# PIC32MZ.net
KiCad netlist of a schematic drawn in Altium Designer
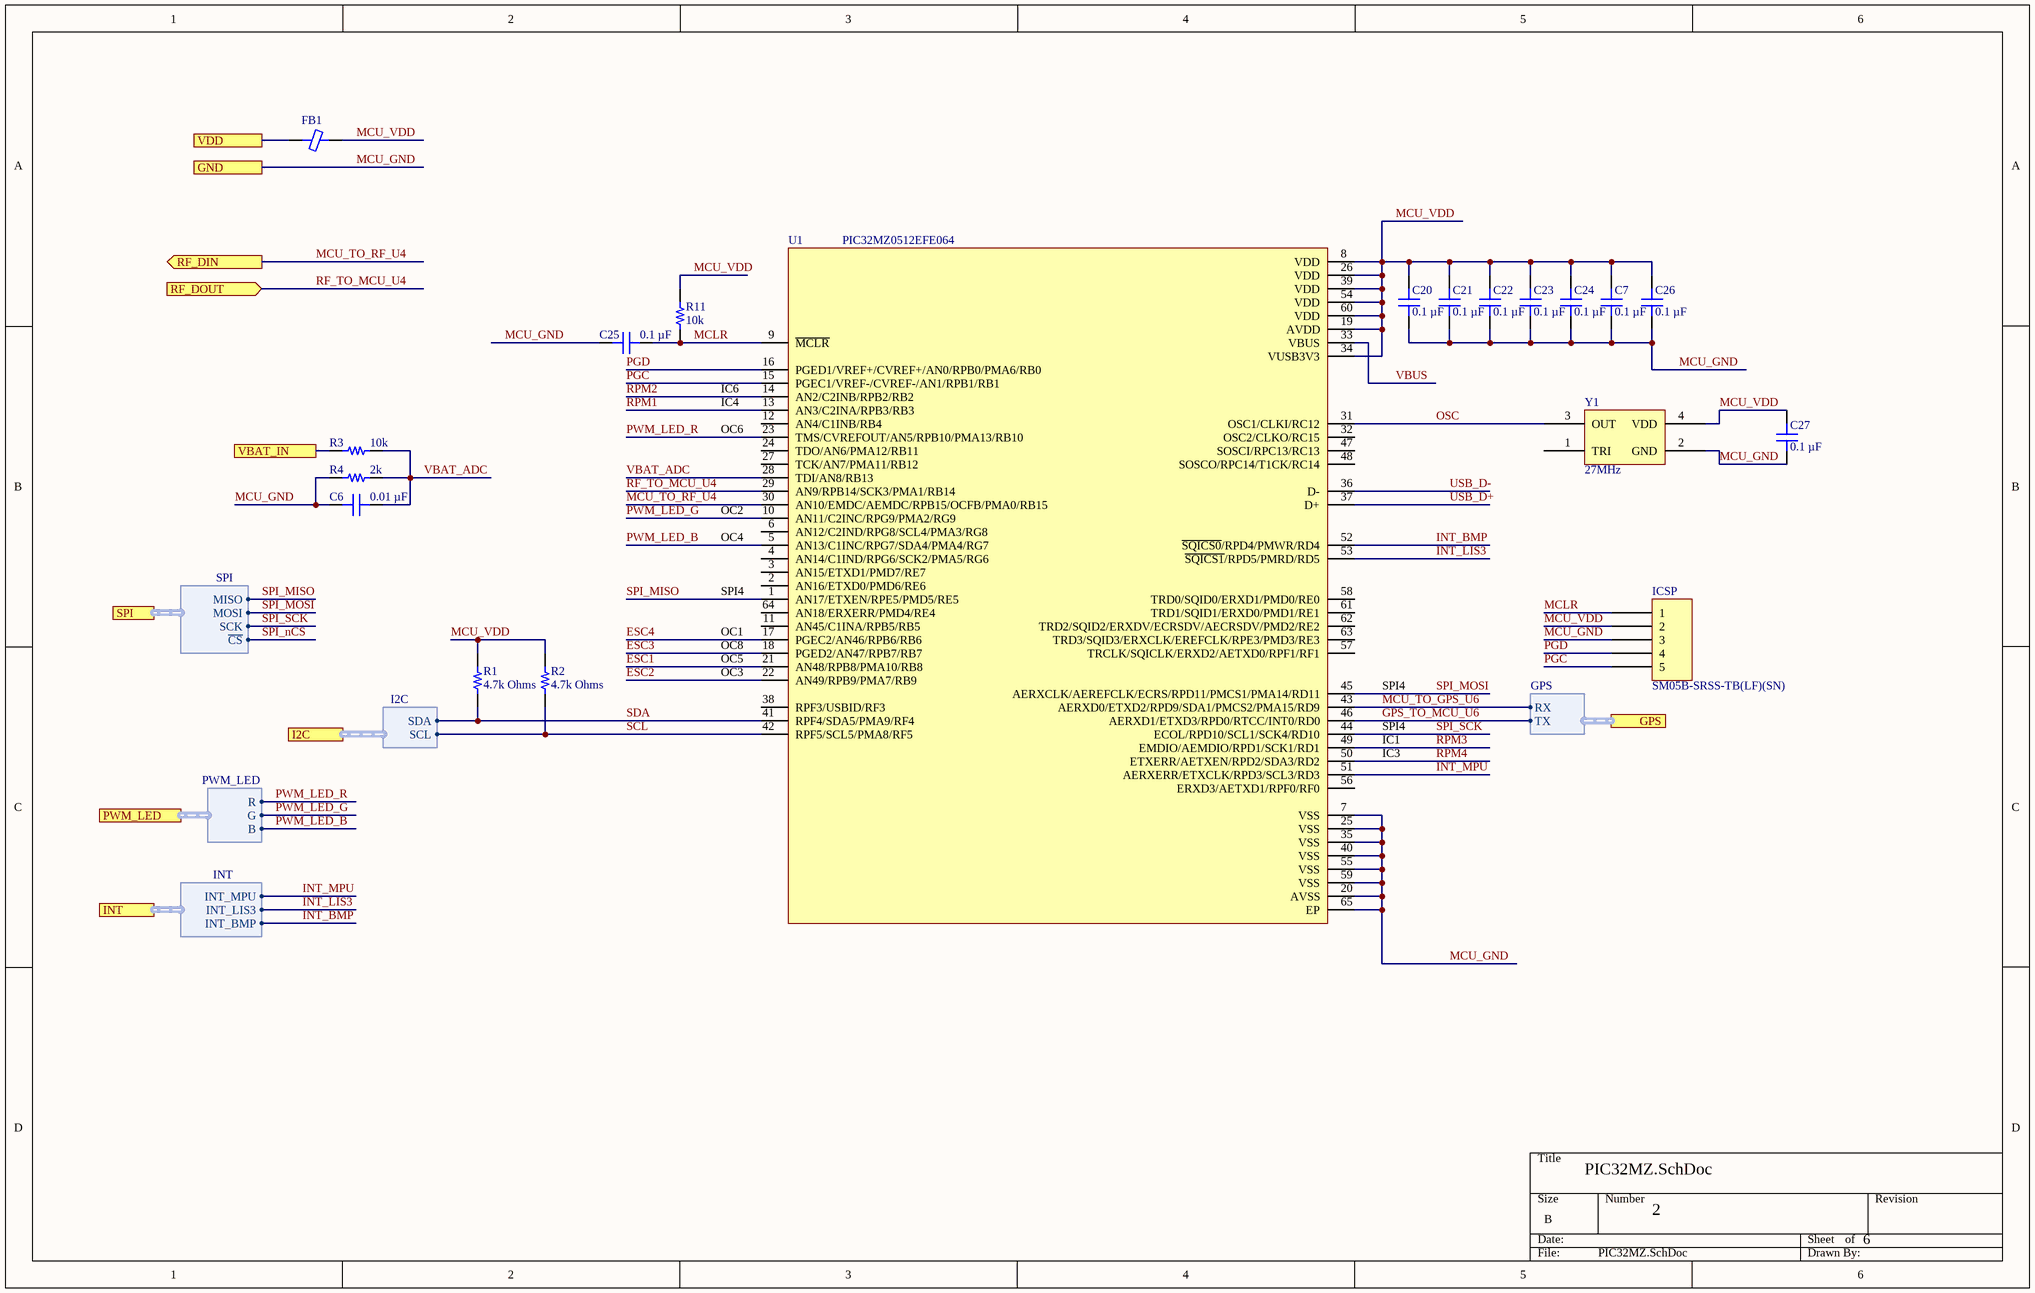
[diagram p0: PIC32MZ.SchDoc]

(export (version "E")
  (design (tool "Eeschema 10.0.6"))
  (components
    (comp (ref "C6")
      (value "0.01 µF")
      (footprint "CAP 0402_1005")
      (description "CAP CER 0.1UF 16V X7R 0402")
      (fields (field (name "PART NUMBER") "C0402C104K4RACAUTO") (field (name "MANUFACTURER") "KEMET"))
      (libsource (lib "Celestial Altium Library - altium_library") (part "Capacitor"))
    )
    (comp (ref "C7")
      (value "0.1 µF")
      (footprint "CAP 0402_1005")
      (description "CAP CER 0.1UF 16V X7R 0402")
      (fields (field (name "PART NUMBER") "C0402C104K4RACAUTO") (field (name "MANUFACTURER") "KEMET"))
      (libsource (lib "Celestial Altium Library - altium_library") (part "Capacitor"))
    )
    (comp (ref "C20")
      (value "0.1 µF")
      (footprint "CAP 0402_1005")
      (description "CAP CER 0.1UF 16V X7R 0402")
      (fields (field (name "PART NUMBER") "C0402C104K4RACAUTO") (field (name "MANUFACTURER") "KEMET"))
      (libsource (lib "Celestial Altium Library - altium_library") (part "Capacitor"))
    )
    (comp (ref "C21")
      (value "0.1 µF")
      (footprint "CAP 0402_1005")
      (description "CAP CER 0.1UF 16V X7R 0402")
      (fields (field (name "PART NUMBER") "C0402C104K4RACAUTO") (field (name "MANUFACTURER") "KEMET"))
      (libsource (lib "Celestial Altium Library - altium_library") (part "Capacitor"))
    )
    (comp (ref "C22")
      (value "0.1 µF")
      (footprint "CAP 0402_1005")
      (description "CAP CER 0.1UF 16V X7R 0402")
      (fields (field (name "PART NUMBER") "C0402C104K4RACAUTO") (field (name "MANUFACTURER") "KEMET"))
      (libsource (lib "Celestial Altium Library - altium_library") (part "Capacitor"))
    )
    (comp (ref "C23")
      (value "0.1 µF")
      (footprint "CAP 0402_1005")
      (description "CAP CER 0.1UF 16V X7R 0402")
      (fields (field (name "PART NUMBER") "C0402C104K4RACAUTO") (field (name "MANUFACTURER") "KEMET"))
      (libsource (lib "Celestial Altium Library - altium_library") (part "Capacitor"))
    )
    (comp (ref "C24")
      (value "0.1 µF")
      (footprint "CAP 0402_1005")
      (description "CAP CER 0.1UF 16V X7R 0402")
      (fields (field (name "PART NUMBER") "C0402C104K4RACAUTO") (field (name "MANUFACTURER") "KEMET"))
      (libsource (lib "Celestial Altium Library - altium_library") (part "Capacitor"))
    )
    (comp (ref "C25")
      (value "0.1 µF")
      (footprint "CAP 0402_1005")
      (description "CAP CER 0.1UF 16V X7R 0402")
      (fields (field (name "PART NUMBER") "C0402C104K4RACAUTO") (field (name "MANUFACTURER") "KEMET"))
      (libsource (lib "Celestial Altium Library - altium_library") (part "Capacitor"))
    )
    (comp (ref "C26")
      (value "0.1 µF")
      (footprint "CAP 0402_1005")
      (description "CAP CER 0.1UF 16V X7R 0402")
      (fields (field (name "PART NUMBER") "C0402C104K4RACAUTO") (field (name "MANUFACTURER") "KEMET"))
      (libsource (lib "Celestial Altium Library - altium_library") (part "Capacitor"))
    )
    (comp (ref "C27")
      (value "0.1 µF")
      (footprint "CAP 0402_1005")
      (description "CAP CER 0.1UF 16V X7R 0402")
      (fields (field (name "PART NUMBER") "C0402C104K4RACAUTO") (field (name "MANUFACTURER") "KEMET"))
      (libsource (lib "Celestial Altium Library - altium_library") (part "Capacitor"))
    )
    (comp (ref "FB1")
      (value "~")
      (footprint "FER 0805_2012")
      (description "FERRITE BEAD 0805 1LN")
      (fields
        (field (name "PART NUMBER") "2508051017Y0")
        (field (name "MANUFACTURER") "Fair-Rite Products Corp.")
      )
      (libsource (lib "Celestial Altium Library - altium_library") (part "Ferrite Chip"))
    )
    (comp (ref "ICSP")
      (value "SM05B-SRSS-TB(LF)(SN)")
      (footprint "JST SM05B-SRSS-TB")
      (description "CONN HEADER SMD R/A 5POS 1MM")
      (fields (field (name "MANUFACTURER") "JST Sales America Inc."))
      (libsource (lib "Celestial Altium Library - altium_library") (part "5 Pin"))
    )
    (comp (ref "R1")
      (value "4.7k Ohms")
      (footprint "RES 0402_1005")
      (description "RES 330 OHM 5% 1/16W 0402")
      (fields (field (name "PART NUMBER") "CRCW0402330RJNEDC") (field (name "MANUFACTURER") "Vishay Dale"))
      (libsource (lib "Celestial Altium Library - altium_library") (part "Resistor"))
    )
    (comp (ref "R2")
      (value "4.7k Ohms")
      (footprint "RES 0402_1005")
      (description "RES 330 OHM 5% 1/16W 0402")
      (fields (field (name "PART NUMBER") "CRCW0402330RJNEDC") (field (name "MANUFACTURER") "Vishay Dale"))
      (libsource (lib "Celestial Altium Library - altium_library") (part "Resistor"))
    )
    (comp (ref "R3")
      (value "10k")
      (footprint "RES 0402_1005")
      (description "RES 330 OHM 5% 1/16W 0402")
      (fields (field (name "PART NUMBER") "CRCW0402330RJNEDC") (field (name "MANUFACTURER") "Vishay Dale"))
      (libsource (lib "Celestial Altium Library - altium_library") (part "Resistor"))
    )
    (comp (ref "R4")
      (value "2k")
      (footprint "RES 0402_1005")
      (description "RES 330 OHM 5% 1/16W 0402")
      (fields (field (name "PART NUMBER") "CRCW0402330RJNEDC") (field (name "MANUFACTURER") "Vishay Dale"))
      (libsource (lib "Celestial Altium Library - altium_library") (part "Resistor"))
    )
    (comp (ref "R11")
      (value "10k")
      (footprint "RES 0402_1005")
      (description "RES 330 OHM 5% 1/16W 0402")
      (fields (field (name "PART NUMBER") "CRCW0402330RJNEDC") (field (name "MANUFACTURER") "Vishay Dale"))
      (libsource (lib "Celestial Altium Library - altium_library") (part "Resistor"))
    )
    (comp (ref "U1")
      (value "PIC32MZ0512EFE064")
      (footprint "QFN50P900X900X100-65N")
      (description "32-bit Microcontrollers - MCU 32-BIT MCU 512KB FL 128KB RAM, No Crypto")
      (fields (field (name "MF") "Microchip") (field (name "MP") "PIC32MZ2048EFG064T-I/PT"))
      (libsource (lib "IC") (part "PIC32MZ0512EFE064-I/PT"))
    )
    (comp (ref "Y1")
      (value "27MHz")
      (footprint "ABRACON ASD")
      (description "XTAL OSC XO 27.0000MHZ HCMOS SMD")
      (fields (field (name "PART NUMBER") "ASD3-27.000MHZ-EC-T") (field (name "MANUFACTURER") "Abracon LLC"))
      (libsource (lib "Celestial Altium Library - altium_library") (part "Abracon XO ASD"))
    )
  )
  (nets
    (net (code "6") (name "/ESC1") (class "Default")
      (node (ref "U1") (pin "21") (pinfunction "AN48/RPB8/PMA10/RB8_21") (pintype "passive"))
    )
    (net (code "7") (name "/ESC2") (class "Default")
      (node (ref "U1") (pin "22") (pinfunction "AN49/RPB9/PMA7/RB9_22") (pintype "passive"))
    )
    (net (code "8") (name "/ESC3") (class "Default")
      (node (ref "U1") (pin "18") (pinfunction "PGED2/AN47/RPB7/RB7_18") (pintype "passive"))
    )
    (net (code "9") (name "/ESC4") (class "Default")
      (node (ref "U1") (pin "17") (pinfunction "PGEC2/AN46/RPB6/RB6_17") (pintype "passive"))
    )
    (net (code "10") (name "/GPS_TO_MCU_U6") (class "Default")
      (node (ref "U1") (pin "46") (pinfunction "AERXD1/ETXD3/RPD0/RTCC/INT0/RD0_46") (pintype "passive"))
    )
    (net (code "11") (name "/INT_BMP") (class "Default")
      (node (ref "U1") (pin "52") (pinfunction "~{SQICS0}/RPD4/PMWR/RD4_52") (pintype "passive"))
    )
    (net (code "12") (name "/INT_LIS3") (class "Default")
      (node (ref "U1") (pin "53") (pinfunction "~{SQICS1}/RPD5/PMRD/RD5_53") (pintype "passive"))
    )
    (net (code "13") (name "/INT_MPU") (class "Default")
      (node (ref "U1") (pin "51") (pinfunction "AERXERR/ETXCLK/RPD3/SCL3/RD3_51") (pintype "passive"))
    )
    (net (code "14") (name "/MCLR") (class "Default")
      (node (ref "C25") (pin "1") (pinfunction "1_1") (pintype "passive"))
      (node (ref "ICSP") (pin "1") (pinfunction "1_1") (pintype "passive"))
      (node (ref "R11") (pin "1") (pinfunction "1_1") (pintype "passive"))
      (node (ref "U1") (pin "9") (pinfunction "~{MCLR}_9") (pintype "passive"))
    )
    (net (code "15") (name "/MCU_GND") (class "Default")
      (node (ref "C20") (pin "1") (pinfunction "1_1") (pintype "passive"))
      (node (ref "C21") (pin "1") (pinfunction "1_1") (pintype "passive"))
      (node (ref "C22") (pin "1") (pinfunction "1_1") (pintype "passive"))
      (node (ref "C23") (pin "1") (pinfunction "1_1") (pintype "passive"))
      (node (ref "C24") (pin "1") (pinfunction "1_1") (pintype "passive"))
      (node (ref "C25") (pin "2") (pinfunction "2_2") (pintype "passive"))
      (node (ref "C26") (pin "1") (pinfunction "1_1") (pintype "passive"))
      (node (ref "C27") (pin "1") (pinfunction "1_1") (pintype "passive"))
      (node (ref "C6") (pin "2") (pinfunction "2_2") (pintype "passive"))
      (node (ref "C7") (pin "1") (pinfunction "1_1") (pintype "passive"))
      (node (ref "ICSP") (pin "3") (pinfunction "3_3") (pintype "passive"))
      (node (ref "R4") (pin "2") (pinfunction "2_2") (pintype "passive"))
      (node (ref "U1") (pin "20") (pinfunction "AVSS_20") (pintype "power_in"))
      (node (ref "U1") (pin "25") (pinfunction "VSS_25") (pintype "power_in"))
      (node (ref "U1") (pin "35") (pinfunction "VSS_35") (pintype "power_in"))
      (node (ref "U1") (pin "40") (pinfunction "VSS_40") (pintype "power_in"))
      (node (ref "U1") (pin "55") (pinfunction "VSS_55") (pintype "power_in"))
      (node (ref "U1") (pin "59") (pinfunction "VSS_59") (pintype "power_in"))
      (node (ref "U1") (pin "65") (pinfunction "EP_65") (pintype "power_in"))
      (node (ref "U1") (pin "7") (pinfunction "VSS_7") (pintype "power_in"))
      (node (ref "Y1") (pin "2") (pinfunction "GND_2") (pintype "passive"))
    )
    (net (code "16") (name "/MCU_TO_GPS_U6") (class "Default")
      (node (ref "U1") (pin "43") (pinfunction "AERXD0/ETXD2/RPD9/SDA1/PMCS2/PMA15/RD9_43") (pintype "passive"))
    )
    (net (code "17") (name "/MCU_TO_RF_U4") (class "Default")
      (node (ref "U1") (pin "30") (pinfunction "AN10/EMDC/AEMDC/RPB15/OCFB/PMA0/RB15_30") (pintype "passive"))
    )
    (net (code "18") (name "/MCU_VDD") (class "Default")
      (node (ref "C20") (pin "2") (pinfunction "2_2") (pintype "passive"))
      (node (ref "C21") (pin "2") (pinfunction "2_2") (pintype "passive"))
      (node (ref "C22") (pin "2") (pinfunction "2_2") (pintype "passive"))
      (node (ref "C23") (pin "2") (pinfunction "2_2") (pintype "passive"))
      (node (ref "C24") (pin "2") (pinfunction "2_2") (pintype "passive"))
      (node (ref "C26") (pin "2") (pinfunction "2_2") (pintype "passive"))
      (node (ref "C27") (pin "2") (pinfunction "2_2") (pintype "passive"))
      (node (ref "C7") (pin "2") (pinfunction "2_2") (pintype "passive"))
      (node (ref "FB1") (pin "2") (pinfunction "2_2") (pintype "passive"))
      (node (ref "ICSP") (pin "2") (pinfunction "2_2") (pintype "passive"))
      (node (ref "R1") (pin "2") (pinfunction "2_2") (pintype "passive"))
      (node (ref "R11") (pin "2") (pinfunction "2_2") (pintype "passive"))
      (node (ref "R2") (pin "2") (pinfunction "2_2") (pintype "passive"))
      (node (ref "U1") (pin "19") (pinfunction "AVDD_19") (pintype "power_in"))
      (node (ref "U1") (pin "26") (pinfunction "VDD_26") (pintype "power_in"))
      (node (ref "U1") (pin "34") (pinfunction "VUSB3V3_34") (pintype "power_in"))
      (node (ref "U1") (pin "39") (pinfunction "VDD_39") (pintype "power_in"))
      (node (ref "U1") (pin "54") (pinfunction "VDD_54") (pintype "power_in"))
      (node (ref "U1") (pin "60") (pinfunction "VDD_60") (pintype "power_in"))
      (node (ref "U1") (pin "8") (pinfunction "VDD_8") (pintype "power_in"))
      (node (ref "Y1") (pin "4") (pinfunction "VDD_4") (pintype "passive"))
    )
    (net (code "19") (name "/OSC") (class "Default")
      (node (ref "U1") (pin "31") (pinfunction "OSC1/CLKI/RC12_31") (pintype "passive"))
      (node (ref "Y1") (pin "3") (pinfunction "OUT_3") (pintype "passive"))
    )
    (net (code "20") (name "/PGC") (class "Default")
      (node (ref "ICSP") (pin "5") (pinfunction "5_5") (pintype "passive"))
      (node (ref "U1") (pin "15") (pinfunction "PGEC1/VREF-/CVREF-/AN1/RPB1/RB1_15") (pintype "passive"))
    )
    (net (code "21") (name "/PGD") (class "Default")
      (node (ref "ICSP") (pin "4") (pinfunction "4_4") (pintype "passive"))
      (node (ref "U1") (pin "16") (pinfunction "PGED1/VREF+/CVREF+/AN0/RPB0/PMA6/RB0_16") (pintype "passive"))
    )
    (net (code "22") (name "/PWM_LED_B") (class "Default")
      (node (ref "U1") (pin "5") (pinfunction "AN13/C1INC/RPG7/SDA4/PMA4/RG7_5") (pintype "passive"))
    )
    (net (code "23") (name "/PWM_LED_G") (class "Default")
      (node (ref "U1") (pin "10") (pinfunction "AN11/C2INC/RPG9/PMA2/RG9_10") (pintype "passive"))
    )
    (net (code "24") (name "/PWM_LED_R") (class "Default")
      (node (ref "U1") (pin "23") (pinfunction "TMS/CVREFOUT/AN5/RPB10/PMA13/RB10_23") (pintype "passive"))
    )
    (net (code "25") (name "/RF_TO_MCU_U4") (class "Default")
      (node (ref "U1") (pin "29") (pinfunction "AN9/RPB14/SCK3/PMA1/RB14_29") (pintype "passive"))
    )
    (net (code "26") (name "/RPM1") (class "Default")
      (node (ref "U1") (pin "13") (pinfunction "AN3/C2INA/RPB3/RB3_13") (pintype "passive"))
    )
    (net (code "27") (name "/RPM2") (class "Default")
      (node (ref "U1") (pin "14") (pinfunction "AN2/C2INB/RPB2/RB2_14") (pintype "passive"))
    )
    (net (code "28") (name "/RPM3") (class "Default")
      (node (ref "U1") (pin "49") (pinfunction "EMDIO/AEMDIO/RPD1/SCK1/RD1_49") (pintype "passive"))
    )
    (net (code "29") (name "/RPM4") (class "Default")
      (node (ref "U1") (pin "50") (pinfunction "ETXERR/AETXEN/RPD2/SDA3/RD2_50") (pintype "passive"))
    )
    (net (code "30") (name "/SCL") (class "Default")
      (node (ref "R2") (pin "1") (pinfunction "1_1") (pintype "passive"))
      (node (ref "U1") (pin "42") (pinfunction "RPF5/SCL5/PMA8/RF5_42") (pintype "passive"))
    )
    (net (code "31") (name "/SDA") (class "Default")
      (node (ref "R1") (pin "1") (pinfunction "1_1") (pintype "passive"))
      (node (ref "U1") (pin "41") (pinfunction "RPF4/SDA5/PMA9/RF4_41") (pintype "passive"))
    )
    (net (code "32") (name "/SPI_MISO") (class "Default")
      (node (ref "U1") (pin "1") (pinfunction "AN17/ETXEN/RPE5/PMD5/RE5_1") (pintype "passive"))
    )
    (net (code "33") (name "/SPI_MOSI") (class "Default")
      (node (ref "U1") (pin "45") (pinfunction "AERXCLK/AEREFCLK/ECRS/RPD11/PMCS1/PMA14/RD11_45") (pintype "passive"))
    )
    (net (code "34") (name "/SPI_SCK") (class "Default")
      (node (ref "U1") (pin "44") (pinfunction "ECOL/RPD10/SCL1/SCK4/RD10_44") (pintype "passive"))
    )
    (net (code "36") (name "/USB_D+") (class "Default")
      (node (ref "U1") (pin "37") (pinfunction "D+_37") (pintype "passive"))
    )
    (net (code "37") (name "/USB_D-") (class "Default")
      (node (ref "U1") (pin "36") (pinfunction "D-_36") (pintype "passive"))
    )
    (net (code "38") (name "/VBAT_ADC") (class "Default")
      (node (ref "C6") (pin "1") (pinfunction "1_1") (pintype "passive"))
      (node (ref "R3") (pin "1") (pinfunction "1_1") (pintype "passive"))
      (node (ref "R4") (pin "1") (pinfunction "1_1") (pintype "passive"))
      (node (ref "U1") (pin "28") (pinfunction "TDI/AN8/RB13_28") (pintype "passive"))
    )
    (net (code "39") (name "/VBAT_IN") (class "Default")
      (node (ref "R3") (pin "2") (pinfunction "2_2") (pintype "passive"))
    )
    (net (code "40") (name "/VBUS") (class "Default")
      (node (ref "U1") (pin "33") (pinfunction "VBUS_33") (pintype "power_in"))
    )
    (net (code "41") (name "/VDD") (class "Default")
      (node (ref "FB1") (pin "1") (pinfunction "1_1") (pintype "passive"))
    )
    (net (code "47") (name "unconnected-(U1-AN4{slash}C1INB{slash}RB4-Pad12)") (class "Default")
      (node (ref "U1") (pin "12") (pinfunction "AN4/C1INB/RB4_12") (pintype "passive"))
    )
    (net (code "48") (name "unconnected-(U1-AN12{slash}C2IND{slash}RPG8{slash}SCL4{slash}PMA3{slash}RG8-Pad6)") (class "Default")
      (node (ref "U1") (pin "6") (pinfunction "AN12/C2IND/RPG8/SCL4/PMA3/RG8_6") (pintype "passive"))
    )
    (net (code "49") (name "unconnected-(U1-AN14{slash}C1IND{slash}RPG6{slash}SCK2{slash}PMA5{slash}RG6-Pad4)") (class "Default")
      (node (ref "U1") (pin "4") (pinfunction "AN14/C1IND/RPG6/SCK2/PMA5/RG6_4") (pintype "passive"))
    )
    (net (code "50") (name "unconnected-(U1-AN15{slash}ETXD1{slash}PMD7{slash}RE7-Pad3)") (class "Default")
      (node (ref "U1") (pin "3") (pinfunction "AN15/ETXD1/PMD7/RE7_3") (pintype "passive"))
    )
    (net (code "51") (name "unconnected-(U1-AN16{slash}ETXD0{slash}PMD6{slash}RE6-Pad2)") (class "Default")
      (node (ref "U1") (pin "2") (pinfunction "AN16/ETXD0/PMD6/RE6_2") (pintype "passive"))
    )
    (net (code "52") (name "unconnected-(U1-AN18{slash}ERXERR{slash}PMD4{slash}RE4-Pad64)") (class "Default")
      (node (ref "U1") (pin "64") (pinfunction "AN18/ERXERR/PMD4/RE4_64") (pintype "passive"))
    )
    (net (code "53") (name "unconnected-(U1-AN45{slash}C1INA{slash}RPB5{slash}RB5-Pad11)") (class "Default")
      (node (ref "U1") (pin "11") (pinfunction "AN45/C1INA/RPB5/RB5_11") (pintype "passive"))
    )
    (net (code "54") (name "unconnected-(U1-ERXD3{slash}AETXD1{slash}RPF0{slash}RF0-Pad56)") (class "Default")
      (node (ref "U1") (pin "56") (pinfunction "ERXD3/AETXD1/RPF0/RF0_56") (pintype "passive"))
    )
    (net (code "55") (name "unconnected-(U1-OSC2{slash}CLKO{slash}RC15-Pad32)") (class "Default")
      (node (ref "U1") (pin "32") (pinfunction "OSC2/CLKO/RC15_32") (pintype "passive"))
    )
    (net (code "56") (name "unconnected-(U1-RPF3{slash}USBID{slash}RF3-Pad38)") (class "Default")
      (node (ref "U1") (pin "38") (pinfunction "RPF3/USBID/RF3_38") (pintype "passive"))
    )
    (net (code "57") (name "unconnected-(U1-SOSCI{slash}RPC13{slash}RC13-Pad47)") (class "Default")
      (node (ref "U1") (pin "47") (pinfunction "SOSCI/RPC13/RC13_47") (pintype "passive"))
    )
    (net (code "58") (name "unconnected-(U1-SOSCO{slash}RPC14{slash}T1CK{slash}RC14-Pad48)") (class "Default")
      (node (ref "U1") (pin "48") (pinfunction "SOSCO/RPC14/T1CK/RC14_48") (pintype "passive"))
    )
    (net (code "59") (name "unconnected-(U1-TCK{slash}AN7{slash}PMA11{slash}RB12-Pad27)") (class "Default")
      (node (ref "U1") (pin "27") (pinfunction "TCK/AN7/PMA11/RB12_27") (pintype "passive"))
    )
    (net (code "60") (name "unconnected-(U1-TDO{slash}AN6{slash}PMA12{slash}RB11-Pad24)") (class "Default")
      (node (ref "U1") (pin "24") (pinfunction "TDO/AN6/PMA12/RB11_24") (pintype "passive"))
    )
    (net (code "61") (name "unconnected-(U1-TRCLK{slash}SQICLK{slash}ERXD2{slash}AETXD0{slash}RPF1{slash}RF1-Pad57)") (class "Default")
      (node (ref "U1") (pin "57") (pinfunction "TRCLK/SQICLK/ERXD2/AETXD0/RPF1/RF1_57") (pintype "passive"))
    )
    (net (code "62") (name "unconnected-(U1-TRD0{slash}SQID0{slash}ERXD1{slash}PMD0{slash}RE0-Pad58)") (class "Default")
      (node (ref "U1") (pin "58") (pinfunction "TRD0/SQID0/ERXD1/PMD0/RE0_58") (pintype "passive"))
    )
    (net (code "63") (name "unconnected-(U1-TRD1{slash}SQID1{slash}ERXD0{slash}PMD1{slash}RE1-Pad61)") (class "Default")
      (node (ref "U1") (pin "61") (pinfunction "TRD1/SQID1/ERXD0/PMD1/RE1_61") (pintype "passive"))
    )
    (net (code "64") (name "unconnected-(U1-TRD2{slash}SQID2{slash}ERXDV{slash}ECRSDV{slash}AECRSDV{slash}PMD2{slash}RE2-Pad62)") (class "Default")
      (node (ref "U1") (pin "62") (pinfunction "TRD2/SQID2/ERXDV/ECRSDV/AECRSDV/PMD2/RE2_62") (pintype "passive"))
    )
    (net (code "65") (name "unconnected-(U1-TRD3{slash}SQID3{slash}ERXCLK{slash}EREFCLK{slash}RPE3{slash}PMD3{slash}RE3-Pad63)") (class "Default")
      (node (ref "U1") (pin "63") (pinfunction "TRD3/SQID3/ERXCLK/EREFCLK/RPE3/PMD3/RE3_63") (pintype "passive"))
    )
    (net (code "66") (name "unconnected-(Y1-TRI-Pad1)") (class "Default")
      (node (ref "Y1") (pin "1") (pinfunction "TRI_1") (pintype "passive"))
    )
  )
)
